# Motherboard.net
KiCad netlist of a schematic drawn in Altium Designer
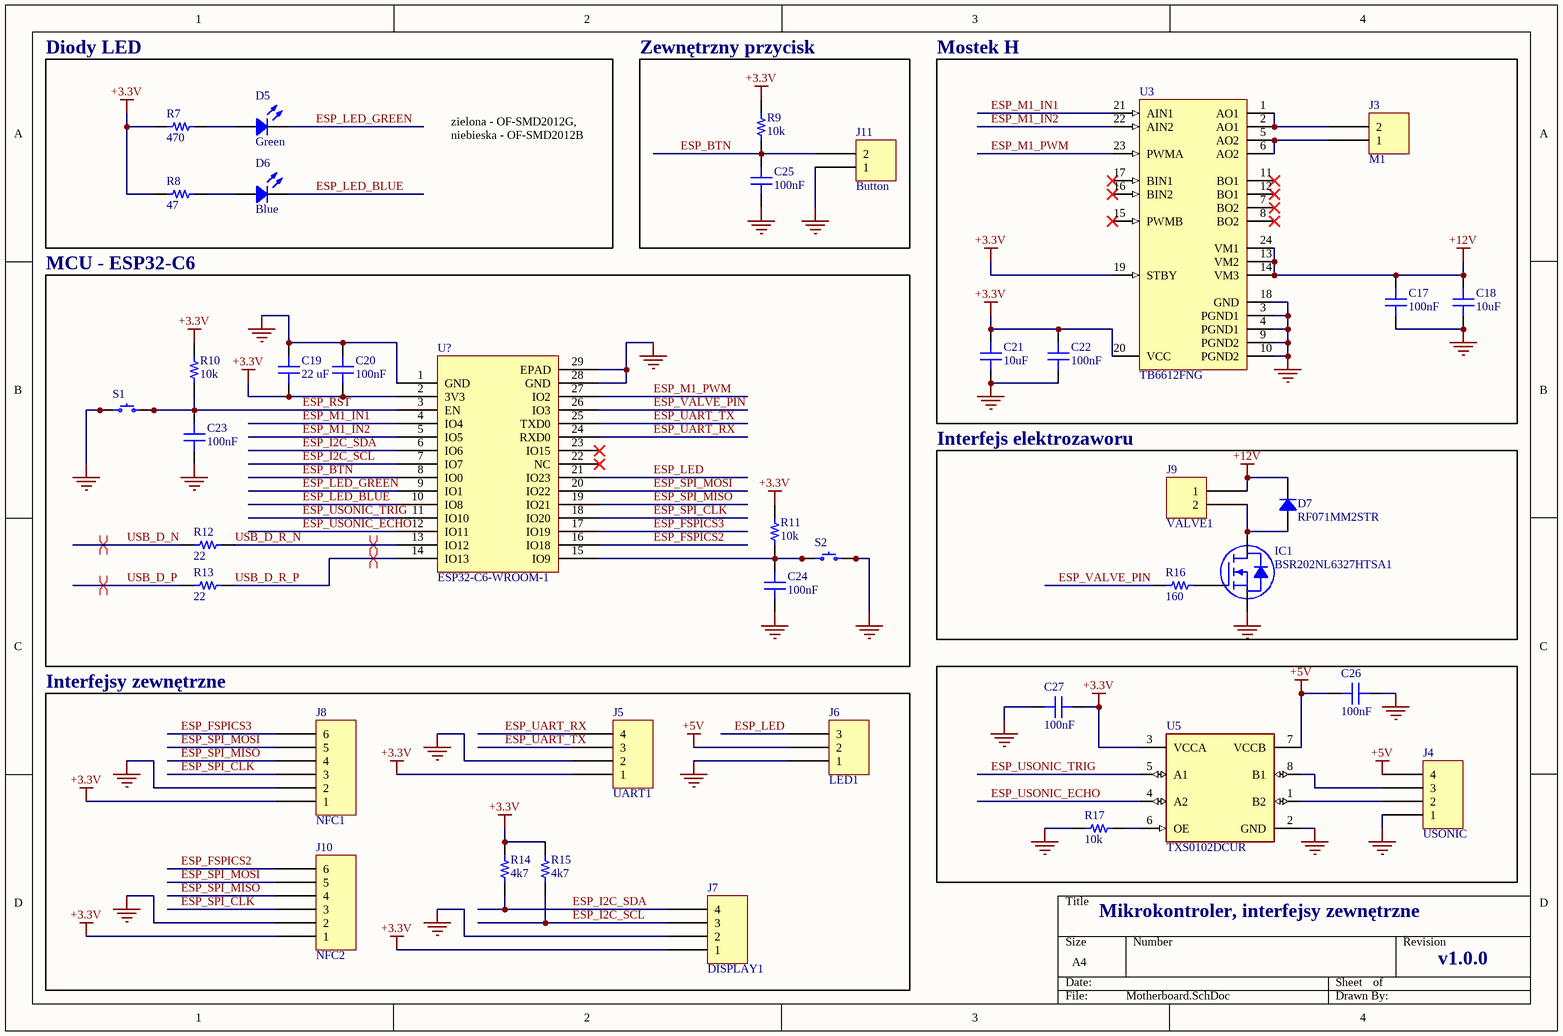
[diagram p0: Motherboard.SchDoc]

(export (version "E")
  (design (tool "Eeschema 10.0.6"))
  (components
    (comp (ref "C17")
      (value "0.1 µF")
      (footprint "CAP 0805_2012")
      (description "CAP CER 0.1UF 50V X7R 0805")
      (fields
        (field (name "PART NUMBER") "CC0805MRX7R9BB104")
        (field (name "CAPACITANCE") "100nF")
        (field (name "MANUFACTURER") "Yageo")
      )
      (libsource (lib "Celestial Altium Library - altium_library") (part "Capacitor"))
    )
    (comp (ref "C18")
      (value "10 µF")
      (footprint "CAP 0805_2012")
      (description "CAP CER 10UF 16V X6S 0805")
      (fields
        (field (name "PART NUMBER") "C2012X6S1C106K125AC")
        (field (name "CAPACITANCE") "10uF")
        (field (name "MANUFACTURER") "TDK Corporation")
      )
      (libsource (lib "Celestial Altium Library - altium_library") (part "Capacitor"))
    )
    (comp (ref "C19")
      (value "22 µF")
      (footprint "CAP 0805_2012")
      (description "CAP CER 22UF 16V X5R 0805")
      (fields
        (field (name "PART NUMBER") "CL21A226KOQNNNG")
        (field (name "CAPACITANCE") "22 uF")
        (field (name "MANUFACTURER") "Samsung Electro-Mechanics")
      )
      (libsource (lib "Celestial Altium Library - altium_library") (part "Capacitor"))
    )
    (comp (ref "C20")
      (value "0.1 µF")
      (footprint "CAP 0805_2012")
      (description "CAP CER 0.1UF 50V X7R 0805")
      (fields
        (field (name "PART NUMBER") "CC0805MRX7R9BB104")
        (field (name "CAPACITANCE") "100nF")
        (field (name "MANUFACTURER") "Yageo")
      )
      (libsource (lib "Celestial Altium Library - altium_library") (part "Capacitor"))
    )
    (comp (ref "C21")
      (value "10 µF")
      (footprint "CAP 0805_2012")
      (description "CAP CER 10UF 16V X6S 0805")
      (fields
        (field (name "PART NUMBER") "C2012X6S1C106K125AC")
        (field (name "CAPACITANCE") "10uF")
        (field (name "MANUFACTURER") "TDK Corporation")
      )
      (libsource (lib "Celestial Altium Library - altium_library") (part "Capacitor"))
    )
    (comp (ref "C22")
      (value "0.1 µF")
      (footprint "CAP 0805_2012")
      (description "CAP CER 0.1UF 50V X7R 0805")
      (fields
        (field (name "PART NUMBER") "CC0805MRX7R9BB104")
        (field (name "CAPACITANCE") "100nF")
        (field (name "MANUFACTURER") "Yageo")
      )
      (libsource (lib "Celestial Altium Library - altium_library") (part "Capacitor"))
    )
    (comp (ref "C23")
      (value "0.1 µF")
      (footprint "CAP 0805_2012")
      (description "CAP CER 0.1UF 50V X7R 0805")
      (fields
        (field (name "PART NUMBER") "CC0805MRX7R9BB104")
        (field (name "CAPACITANCE") "100nF")
        (field (name "MANUFACTURER") "Yageo")
      )
      (libsource (lib "Celestial Altium Library - altium_library") (part "Capacitor"))
    )
    (comp (ref "C24")
      (value "0.1 µF")
      (footprint "CAP 0805_2012")
      (description "CAP CER 0.1UF 50V X7R 0805")
      (fields
        (field (name "PART NUMBER") "CC0805MRX7R9BB104")
        (field (name "CAPACITANCE") "100nF")
        (field (name "MANUFACTURER") "Yageo")
      )
      (libsource (lib "Celestial Altium Library - altium_library") (part "Capacitor"))
    )
    (comp (ref "C25")
      (value "0.1 µF")
      (footprint "CAP 0805_2012")
      (description "CAP CER 0.1UF 50V X7R 0805")
      (fields
        (field (name "PART NUMBER") "CC0805MRX7R9BB104")
        (field (name "CAPACITANCE") "100nF")
        (field (name "MANUFACTURER") "Yageo")
      )
      (libsource (lib "Celestial Altium Library - altium_library") (part "Capacitor"))
    )
    (comp (ref "C26")
      (value "0.1 µF")
      (footprint "CAP 0805_2012")
      (description "CAP CER 0.1UF 50V X7R 0805")
      (fields
        (field (name "PART NUMBER") "CC0805MRX7R9BB104")
        (field (name "CAPACITANCE") "100nF")
        (field (name "MANUFACTURER") "Yageo")
      )
      (libsource (lib "Celestial Altium Library - altium_library") (part "Capacitor"))
    )
    (comp (ref "C27")
      (value "0.1 µF")
      (footprint "CAP 0805_2012")
      (description "CAP CER 0.1UF 50V X7R 0805")
      (fields
        (field (name "PART NUMBER") "CC0805MRX7R9BB104")
        (field (name "CAPACITANCE") "100nF")
        (field (name "MANUFACTURER") "Yageo")
      )
      (libsource (lib "Celestial Altium Library - altium_library") (part "Capacitor"))
    )
    (comp (ref "D5")
      (value "Green")
      (footprint "LED 0805_2012 GREEN")
      (description "LED GREEN CLEAR CHIP SMD")
      (fields (field (name "PART NUMBER") "APHCM2012CGCK-F01") (field (name "MANUFACTURER") "Kingbright"))
      (libsource (lib "Celestial Altium Library - altium_library") (part "LED"))
    )
    (comp (ref "D6")
      (value "Blue")
      (footprint "LED 0805_2012 BLUE")
      (description "LED BLUE CLEAR 2012 SMD")
      (fields (field (name "PART NUMBER") "SMLMN2BCTT86C") (field (name "MANUFACTURER") "Rohm Semiconductor"))
      (libsource (lib "Celestial Altium Library - altium_library") (part "LED"))
    )
    (comp (ref "D7")
      (value "RF071MM2STR")
      (footprint "SOD123F")
      (description "DIODE GEN PURP 200V 700MA PMDU")
      (fields (field (name "MANUFACTURER") "Rohm Semiconductor"))
      (libsource (lib "Celestial Altium Library - altium_library") (part "Diode"))
    )
    (comp (ref "IC1")
      (value "BSR202NL6327HTSA1")
      (footprint "INFINEON SOT-23-3")
      (description "MOSFET N-CH 20V 3.8A SC59")
      (fields (field (name "MANUFACTURER") "Infineon Technologies"))
      (libsource (lib "Celestial Altium Library - altium_library") (part "INFINEON MOSFET N-CH SOT-23-3 GSD"))
    )
    (comp (ref "J3")
      (value "M1")
      (footprint "MOLEX KK 0022272021")
      (description "CONN HEADER VERT 2POS 2.54MM")
      (fields (field (name "PART NUMBER") "0022272021") (field (name "MANUFACTURER") "Molex"))
      (libsource (lib "Celestial Altium Library - altium_library") (part "2 Pin"))
    )
    (comp (ref "J4")
      (value "USONIC")
      (footprint "MOLEX KK 0022272041")
      (description "CONN HEADER VERT 4POS 2.54MM")
      (fields (field (name "PART NUMBER") "0022272041") (field (name "MANUFACTURER") "Molex"))
      (libsource (lib "Celestial Altium Library - altium_library") (part "4 Pin"))
    )
    (comp (ref "J5")
      (value "UART1")
      (footprint "MOLEX KK 0022272041")
      (description "CONN HEADER VERT 4POS 2.54MM")
      (fields (field (name "PART NUMBER") "0022272041") (field (name "MANUFACTURER") "Molex"))
      (libsource (lib "Celestial Altium Library - altium_library") (part "4 Pin"))
    )
    (comp (ref "J6")
      (value "LED1")
      (footprint "MOLEX KK 0022272031")
      (description "CONN HEADER VERT 3POS 2.54MM")
      (fields (field (name "PART NUMBER") "0022272031") (field (name "MANUFACTURER") "Molex"))
      (libsource (lib "Celestial Altium Library - altium_library") (part "3 Pin"))
    )
    (comp (ref "J7")
      (value "DISPLAY1")
      (footprint "MOLEX KK 0022272041")
      (description "CONN HEADER VERT 4POS 2.54MM")
      (fields (field (name "PART NUMBER") "0022272041") (field (name "MANUFACTURER") "Molex"))
      (libsource (lib "Celestial Altium Library - altium_library") (part "4 Pin"))
    )
    (comp (ref "J8")
      (value "NFC1")
      (footprint "MOLEX KK 0022272061")
      (description "CONN HEADER VERT 6POS 2.54MM")
      (fields (field (name "PART NUMBER") "0022272061") (field (name "MANUFACTURER") "Molex"))
      (libsource (lib "Celestial Altium Library - altium_library") (part "6 Pin"))
    )
    (comp (ref "J9")
      (value "VALVE1")
      (footprint "MOLEX KK 0022272021")
      (description "CONN HEADER VERT 2POS 2.54MM")
      (fields (field (name "PART NUMBER") "0022272021") (field (name "MANUFACTURER") "Molex"))
      (libsource (lib "") (part "2 Pin_1"))
    )
    (comp (ref "J10")
      (value "NFC2")
      (footprint "MOLEX KK 0022272061")
      (description "CONN HEADER VERT 6POS 2.54MM")
      (fields (field (name "PART NUMBER") "0022272061") (field (name "MANUFACTURER") "Molex"))
      (libsource (lib "Celestial Altium Library - altium_library") (part "6 Pin"))
    )
    (comp (ref "J11")
      (value "Button")
      (footprint "MOLEX KK 0022272021")
      (description "CONN HEADER VERT 2POS 2.54MM")
      (fields (field (name "PART NUMBER") "0022272021") (field (name "MANUFACTURER") "Molex"))
      (libsource (lib "Celestial Altium Library - altium_library") (part "2 Pin"))
    )
    (comp (ref "R7")
      (value "470")
      (footprint "RES 0805_2012")
      (description "RES 470 OHM 1% 1/3W 0805")
      (fields
        (field (name "PART NUMBER") "CRGP0805F470R")
        (field (name "MANUFACTURER") "TE Connectivity Passive Product")
      )
      (libsource (lib "Celestial Altium Library - altium_library") (part "Resistor"))
    )
    (comp (ref "R8")
      (value "47")
      (footprint "RES 0805_2012")
      (description "RES 47 OHM 1% 1/3W 0805")
      (fields
        (field (name "PART NUMBER") "CRGP0805F47R")
        (field (name "MANUFACTURER") "TE Connectivity Passive Product")
      )
      (libsource (lib "Celestial Altium Library - altium_library") (part "Resistor"))
    )
    (comp (ref "R9")
      (value "10k")
      (footprint "RES 0805_2012")
      (description "RES 10K OHM 0.1% 1/10W 0805")
      (fields
        (field (name "PART NUMBER") "RNCS0805BKE10K0")
        (field (name "MANUFACTURER") "Stackpole Electronics Inc")
      )
      (libsource (lib "Celestial Altium Library - altium_library") (part "Resistor"))
    )
    (comp (ref "R10")
      (value "10k")
      (footprint "RES 0805_2012")
      (description "RES 10K OHM 0.1% 1/10W 0805")
      (fields
        (field (name "PART NUMBER") "RNCS0805BKE10K0")
        (field (name "MANUFACTURER") "Stackpole Electronics Inc")
      )
      (libsource (lib "Celestial Altium Library - altium_library") (part "Resistor"))
    )
    (comp (ref "R11")
      (value "10k")
      (footprint "RES 0805_2012")
      (description "RES 10K OHM 0.1% 1/10W 0805")
      (fields
        (field (name "PART NUMBER") "RNCS0805BKE10K0")
        (field (name "MANUFACTURER") "Stackpole Electronics Inc")
      )
      (libsource (lib "Celestial Altium Library - altium_library") (part "Resistor"))
    )
    (comp (ref "R12")
      (value "22")
      (footprint "RES 0805_2012")
      (description "RES SMD 22 OHM 0.1% 1/10W 0805")
      (fields
        (field (name "PART NUMBER") "CPF0805B22RE1")
        (field (name "MANUFACTURER") "TE Connectivity Passive Product")
      )
      (libsource (lib "Celestial Altium Library - altium_library") (part "Resistor"))
    )
    (comp (ref "R13")
      (value "22")
      (footprint "RES 0805_2012")
      (description "RES SMD 22 OHM 0.1% 1/10W 0805")
      (fields
        (field (name "PART NUMBER") "CPF0805B22RE1")
        (field (name "MANUFACTURER") "TE Connectivity Passive Product")
      )
      (libsource (lib "Celestial Altium Library - altium_library") (part "Resistor"))
    )
    (comp (ref "R14")
      (value "4k7")
      (footprint "RES 0805_2012")
      (description "RES SMD 4.7K OHM 5% 1/2W 0805")
      (fields (field (name "PART NUMBER") "RCS08054K70JNEA") (field (name "MANUFACTURER") "Vishay Dale"))
      (libsource (lib "Celestial Altium Library - altium_library") (part "Resistor"))
    )
    (comp (ref "R15")
      (value "4k7")
      (footprint "RES 0805_2012")
      (description "RES SMD 4.7K OHM 5% 1/2W 0805")
      (fields (field (name "PART NUMBER") "RCS08054K70JNEA") (field (name "MANUFACTURER") "Vishay Dale"))
      (libsource (lib "Celestial Altium Library - altium_library") (part "Resistor"))
    )
    (comp (ref "R16")
      (value "160")
      (footprint "YAGEO RES 0805_2012")
      (description "RES SMD 160 OHM 0.1% 1/8W 0805")
      (fields (field (name "PART NUMBER") "RT0805BRD07160RL") (field (name "MANUFACTURER") "Yageo"))
      (libsource (lib "Celestial Altium Library - altium_library") (part "Resistor"))
    )
    (comp (ref "R17")
      (value "10k")
      (footprint "RES 0805_2012")
      (description "RES 10K OHM 0.1% 1/10W 0805")
      (fields
        (field (name "PART NUMBER") "RNCS0805BKE10K0")
        (field (name "MANUFACTURER") "Stackpole Electronics Inc")
      )
      (libsource (lib "Celestial Altium Library - altium_library") (part "Resistor"))
    )
    (comp (ref "S1")
      (value "FSM6JSMAASTR")
      (footprint "TE FSM6JSMA")
      (description "SWITCH TACTILE SPST-NO 0.05A 24V")
      (fields (field (name "MANUFACTURER") "TE Connectivity ALCOSWITCH Switches"))
      (libsource (lib "Celestial Altium Library - altium_library") (part "SPST-NO 4 PIN"))
    )
    (comp (ref "S2")
      (value "FSM6JSMAASTR")
      (footprint "TE FSM6JSMA")
      (description "SWITCH TACTILE SPST-NO 0.05A 24V")
      (fields (field (name "MANUFACTURER") "TE Connectivity ALCOSWITCH Switches"))
      (libsource (lib "Celestial Altium Library - altium_library") (part "SPST-NO 4 PIN"))
    )
    (comp (ref "U3")
      (value "TB6612FNG")
      (footprint "TOSH-SSOP-24_M")
      (description "Driver IC for Dual DC Motor, 15 V, -20 to 85 degC, 24-Pin SSOP, RoHS, Tape and Reel")
      (libsource (lib "Altium Content Vault") (part "TOSH-TB6612FNG-SOP-24"))
    )
    (comp (ref "U4")
      (value "ESP32-C6-WROOM-1")
      (footprint "ESP32-C6-WROOM1")
      (libsource (lib "My_integrated_circuits") (part "ESP32-C6-WROOM-1"))
    )
    (comp (ref "U5")
      (value "TXS0102DCUR")
      (footprint "FP-DCU0008A-MFG")
      (description "TXS0102 2-Bit Bidirectional Voltage-Level Translator for Open-Drain and Push-Pull Applications")
      (fields (field (name "MANUFACTURER") "Texas Instruments"))
      (libsource (lib "Altium Content Vault") (part "7edb3aeb21a89e92b7ef258fabac7d1"))
    )
  )
  (nets
    (net (code "1") (name "+3.3V") (class "Default")
      (node (ref "C19") (pin "1") (pinfunction "1_1") (pintype "passive"))
      (node (ref "C20") (pin "1") (pinfunction "1_1") (pintype "passive"))
      (node (ref "C21") (pin "2") (pinfunction "2_2") (pintype "passive"))
      (node (ref "C22") (pin "1") (pinfunction "1_1") (pintype "passive"))
      (node (ref "C27") (pin "2") (pinfunction "2_2") (pintype "passive"))
      (node (ref "J10") (pin "1") (pinfunction "1_1") (pintype "passive"))
      (node (ref "J5") (pin "1") (pinfunction "1_1") (pintype "passive"))
      (node (ref "J7") (pin "1") (pinfunction "1_1") (pintype "passive"))
      (node (ref "J8") (pin "1") (pinfunction "1_1") (pintype "passive"))
      (node (ref "R10") (pin "2") (pinfunction "2_2") (pintype "passive"))
      (node (ref "R11") (pin "2") (pinfunction "2_2") (pintype "passive"))
      (node (ref "R14") (pin "2") (pinfunction "2_2") (pintype "passive"))
      (node (ref "R15") (pin "2") (pinfunction "2_2") (pintype "passive"))
      (node (ref "R7") (pin "1") (pinfunction "1_1") (pintype "passive"))
      (node (ref "R8") (pin "1") (pinfunction "1_1") (pintype "passive"))
      (node (ref "R9") (pin "2") (pinfunction "2_2") (pintype "passive"))
      (node (ref "U3") (pin "19") (pinfunction "STBY_19") (pintype "input"))
      (node (ref "U3") (pin "20") (pinfunction "VCC_20") (pintype "power_in"))
      (node (ref "U4") (pin "2") (pinfunction "3V3_2") (pintype "passive"))
      (node (ref "U5") (pin "3") (pinfunction "VCCA_3") (pintype "power_in"))
    )
    (net (code "2") (name "+5V") (class "Default")
      (node (ref "C26") (pin "1") (pinfunction "1_1") (pintype "passive"))
      (node (ref "J4") (pin "4") (pinfunction "4_4") (pintype "passive"))
      (node (ref "J6") (pin "2") (pinfunction "2_2") (pintype "passive"))
      (node (ref "U5") (pin "7") (pinfunction "VCCB_7") (pintype "power_in"))
    )
    (net (code "3") (name "+12V") (class "Default")
      (node (ref "C17") (pin "1") (pinfunction "1_1") (pintype "passive"))
      (node (ref "C18") (pin "2") (pinfunction "2_2") (pintype "passive"))
      (node (ref "D7") (pin "2") (pinfunction "2_2") (pintype "passive"))
      (node (ref "J9") (pin "1") (pinfunction "1_1") (pintype "passive"))
      (node (ref "U3") (pin "13") (pinfunction "VM2_13") (pintype "power_in"))
      (node (ref "U3") (pin "14") (pinfunction "VM3_14") (pintype "power_in"))
      (node (ref "U3") (pin "24") (pinfunction "VM1_24") (pintype "power_in"))
    )
    (net (code "4") (name "/ESP_BTN") (class "Default")
      (node (ref "C25") (pin "2") (pinfunction "2_2") (pintype "passive"))
      (node (ref "J11") (pin "2") (pinfunction "2_2") (pintype "passive"))
      (node (ref "R9") (pin "1") (pinfunction "1_1") (pintype "passive"))
      (node (ref "U4") (pin "8") (pinfunction "IO0_8") (pintype "passive"))
    )
    (net (code "5") (name "/ESP_FSPICS2") (class "Default")
      (node (ref "J10") (pin "6") (pinfunction "6_6") (pintype "passive"))
      (node (ref "U4") (pin "16") (pinfunction "IO18_16") (pintype "passive"))
    )
    (net (code "6") (name "/ESP_FSPICS3") (class "Default")
      (node (ref "J8") (pin "6") (pinfunction "6_6") (pintype "passive"))
      (node (ref "U4") (pin "17") (pinfunction "IO19_17") (pintype "passive"))
    )
    (net (code "7") (name "/ESP_I2C_SCL") (class "Default")
      (node (ref "J7") (pin "3") (pinfunction "3_3") (pintype "passive"))
      (node (ref "R15") (pin "1") (pinfunction "1_1") (pintype "passive"))
      (node (ref "U4") (pin "7") (pinfunction "IO7_7") (pintype "passive"))
    )
    (net (code "8") (name "/ESP_I2C_SDA") (class "Default")
      (node (ref "J7") (pin "4") (pinfunction "4_4") (pintype "passive"))
      (node (ref "R14") (pin "1") (pinfunction "1_1") (pintype "passive"))
      (node (ref "U4") (pin "6") (pinfunction "IO6_6") (pintype "passive"))
    )
    (net (code "9") (name "/ESP_LED") (class "Default")
      (node (ref "J6") (pin "3") (pinfunction "3_3") (pintype "passive"))
      (node (ref "U4") (pin "21") (pinfunction "IO23_21") (pintype "passive"))
    )
    (net (code "10") (name "/ESP_LED_BLUE") (class "Default")
      (node (ref "D6") (pin "2") (pinfunction "2_2") (pintype "passive"))
      (node (ref "U4") (pin "10") (pinfunction "IO8_10") (pintype "passive"))
    )
    (net (code "11") (name "/ESP_LED_GREEN") (class "Default")
      (node (ref "D5") (pin "2") (pinfunction "2_2") (pintype "passive"))
      (node (ref "U4") (pin "9") (pinfunction "IO1_9") (pintype "passive"))
    )
    (net (code "12") (name "/ESP_M1_IN1") (class "Default")
      (node (ref "U3") (pin "21") (pinfunction "AIN1_21") (pintype "input"))
      (node (ref "U4") (pin "4") (pinfunction "IO4_4") (pintype "passive"))
    )
    (net (code "13") (name "/ESP_M1_IN2") (class "Default")
      (node (ref "U3") (pin "22") (pinfunction "AIN2_22") (pintype "input"))
      (node (ref "U4") (pin "5") (pinfunction "IO5_5") (pintype "passive"))
    )
    (net (code "14") (name "/ESP_M1_PWM") (class "Default")
      (node (ref "U3") (pin "23") (pinfunction "PWMA_23") (pintype "input"))
      (node (ref "U4") (pin "27") (pinfunction "IO2_27") (pintype "passive"))
    )
    (net (code "15") (name "/ESP_RST") (class "Default")
      (node (ref "C23") (pin "2") (pinfunction "2_2") (pintype "passive"))
      (node (ref "R10") (pin "1") (pinfunction "1_1") (pintype "passive"))
      (node (ref "S1") (pin "3") (pinfunction "3_3") (pintype "passive"))
      (node (ref "S1") (pin "4") (pinfunction "4_4") (pintype "passive"))
      (node (ref "U4") (pin "3") (pinfunction "EN_3") (pintype "passive"))
    )
    (net (code "16") (name "/ESP_SPI_CLK") (class "Default")
      (node (ref "J10") (pin "3") (pinfunction "3_3") (pintype "passive"))
      (node (ref "J8") (pin "3") (pinfunction "3_3") (pintype "passive"))
      (node (ref "U4") (pin "18") (pinfunction "IO20_18") (pintype "passive"))
    )
    (net (code "17") (name "/ESP_SPI_MISO") (class "Default")
      (node (ref "J10") (pin "4") (pinfunction "4_4") (pintype "passive"))
      (node (ref "J8") (pin "4") (pinfunction "4_4") (pintype "passive"))
      (node (ref "U4") (pin "19") (pinfunction "IO21_19") (pintype "passive"))
    )
    (net (code "18") (name "/ESP_SPI_MOSI") (class "Default")
      (node (ref "J10") (pin "5") (pinfunction "5_5") (pintype "passive"))
      (node (ref "J8") (pin "5") (pinfunction "5_5") (pintype "passive"))
      (node (ref "U4") (pin "20") (pinfunction "IO22_20") (pintype "passive"))
    )
    (net (code "19") (name "/ESP_UART_RX") (class "Default")
      (node (ref "J5") (pin "4") (pinfunction "4_4") (pintype "passive"))
      (node (ref "U4") (pin "24") (pinfunction "RXD0_24") (pintype "passive"))
    )
    (net (code "20") (name "/ESP_UART_TX") (class "Default")
      (node (ref "J5") (pin "3") (pinfunction "3_3") (pintype "passive"))
      (node (ref "U4") (pin "25") (pinfunction "TXD0_25") (pintype "passive"))
    )
    (net (code "21") (name "/ESP_USONIC_ECHO") (class "Default")
      (node (ref "U4") (pin "12") (pinfunction "IO11_12") (pintype "passive"))
      (node (ref "U5") (pin "4") (pinfunction "A2_4") (pintype "bidirectional"))
    )
    (net (code "22") (name "/ESP_USONIC_TRIG") (class "Default")
      (node (ref "U4") (pin "11") (pinfunction "IO10_11") (pintype "passive"))
      (node (ref "U5") (pin "5") (pinfunction "A1_5") (pintype "bidirectional"))
    )
    (net (code "23") (name "/ESP_VALVE_PIN") (class "Default")
      (node (ref "R16") (pin "1") (pinfunction "1_1") (pintype "passive"))
      (node (ref "U4") (pin "26") (pinfunction "IO3_26") (pintype "passive"))
    )
    (net (code "24") (name "/USB_D_N") (class "Default")
      (node (ref "R12") (pin "1") (pinfunction "1_1") (pintype "passive"))
    )
    (net (code "25") (name "/USB_D_P") (class "Default")
      (node (ref "R13") (pin "1") (pinfunction "1_1") (pintype "passive"))
    )
    (net (code "26") (name "/USB_D_R_N") (class "Default")
      (node (ref "R12") (pin "2") (pinfunction "2_2") (pintype "passive"))
      (node (ref "U4") (pin "13") (pinfunction "IO12_13") (pintype "passive"))
    )
    (net (code "27") (name "/USB_D_R_P") (class "Default")
      (node (ref "R13") (pin "2") (pinfunction "2_2") (pintype "passive"))
      (node (ref "U4") (pin "14") (pinfunction "IO13_14") (pintype "passive"))
    )
    (net (code "28") (name "GND") (class "Default")
      (node (ref "C17") (pin "2") (pinfunction "2_2") (pintype "passive"))
      (node (ref "C18") (pin "1") (pinfunction "1_1") (pintype "passive"))
      (node (ref "C19") (pin "2") (pinfunction "2_2") (pintype "passive"))
      (node (ref "C20") (pin "2") (pinfunction "2_2") (pintype "passive"))
      (node (ref "C21") (pin "1") (pinfunction "1_1") (pintype "passive"))
      (node (ref "C22") (pin "2") (pinfunction "2_2") (pintype "passive"))
      (node (ref "C23") (pin "1") (pinfunction "1_1") (pintype "passive"))
      (node (ref "C24") (pin "1") (pinfunction "1_1") (pintype "passive"))
      (node (ref "C25") (pin "1") (pinfunction "1_1") (pintype "passive"))
      (node (ref "C26") (pin "2") (pinfunction "2_2") (pintype "passive"))
      (node (ref "C27") (pin "1") (pinfunction "1_1") (pintype "passive"))
      (node (ref "IC1") (pin "2") (pinfunction "S_2") (pintype "passive"))
      (node (ref "J10") (pin "2") (pinfunction "2_2") (pintype "passive"))
      (node (ref "J11") (pin "1") (pinfunction "1_1") (pintype "passive"))
      (node (ref "J4") (pin "1") (pinfunction "1_1") (pintype "passive"))
      (node (ref "J5") (pin "2") (pinfunction "2_2") (pintype "passive"))
      (node (ref "J6") (pin "1") (pinfunction "1_1") (pintype "passive"))
      (node (ref "J7") (pin "2") (pinfunction "2_2") (pintype "passive"))
      (node (ref "J8") (pin "2") (pinfunction "2_2") (pintype "passive"))
      (node (ref "R17") (pin "1") (pinfunction "1_1") (pintype "passive"))
      (node (ref "S1") (pin "1") (pinfunction "1_1") (pintype "passive"))
      (node (ref "S1") (pin "2") (pinfunction "2_2") (pintype "passive"))
      (node (ref "S2") (pin "3") (pinfunction "3_3") (pintype "passive"))
      (node (ref "S2") (pin "4") (pinfunction "4_4") (pintype "passive"))
      (node (ref "U3") (pin "10") (pinfunction "PGND2_10") (pintype "power_in"))
      (node (ref "U3") (pin "18") (pinfunction "GND_18") (pintype "power_in"))
      (node (ref "U3") (pin "3") (pinfunction "PGND1_3") (pintype "power_in"))
      (node (ref "U3") (pin "4") (pinfunction "PGND1_4") (pintype "power_in"))
      (node (ref "U3") (pin "9") (pinfunction "PGND2_9") (pintype "power_in"))
      (node (ref "U4") (pin "1") (pinfunction "GND_1") (pintype "passive"))
      (node (ref "U4") (pin "28") (pinfunction "GND_28") (pintype "passive"))
      (node (ref "U4") (pin "29") (pinfunction "EPAD_29") (pintype "passive"))
      (node (ref "U5") (pin "2") (pinfunction "GND_2") (pintype "power_in"))
    )
    (net (code "29") (name "Net-(D5-Pad1)") (class "Default")
      (node (ref "D5") (pin "1") (pinfunction "1_1") (pintype "passive"))
      (node (ref "R7") (pin "2") (pinfunction "2_2") (pintype "passive"))
    )
    (net (code "30") (name "Net-(D6-Pad1)") (class "Default")
      (node (ref "D6") (pin "1") (pinfunction "1_1") (pintype "passive"))
      (node (ref "R8") (pin "2") (pinfunction "2_2") (pintype "passive"))
    )
    (net (code "31") (name "Net-(IC1-D)") (class "Default")
      (node (ref "D7") (pin "1") (pinfunction "1_1") (pintype "passive"))
      (node (ref "IC1") (pin "3") (pinfunction "D_3") (pintype "passive"))
      (node (ref "J9") (pin "2") (pinfunction "2_2") (pintype "passive"))
    )
    (net (code "32") (name "Net-(IC1-G)") (class "Default")
      (node (ref "IC1") (pin "1") (pinfunction "G_1") (pintype "passive"))
      (node (ref "R16") (pin "2") (pinfunction "2_2") (pintype "passive"))
    )
    (net (code "33") (name "Net-(J3-Pad1)") (class "Default")
      (node (ref "J3") (pin "1") (pinfunction "1_1") (pintype "passive"))
      (node (ref "U3") (pin "5") (pinfunction "AO2_5") (pintype "tri_state"))
      (node (ref "U3") (pin "6") (pinfunction "AO2_6") (pintype "tri_state"))
    )
    (net (code "34") (name "Net-(J3-Pad2)") (class "Default")
      (node (ref "J3") (pin "2") (pinfunction "2_2") (pintype "passive"))
      (node (ref "U3") (pin "1") (pinfunction "AO1_1") (pintype "tri_state"))
      (node (ref "U3") (pin "2") (pinfunction "AO1_2") (pintype "tri_state"))
    )
    (net (code "35") (name "Net-(U4-IO9)") (class "Default")
      (node (ref "C24") (pin "2") (pinfunction "2_2") (pintype "passive"))
      (node (ref "R11") (pin "1") (pinfunction "1_1") (pintype "passive"))
      (node (ref "S2") (pin "1") (pinfunction "1_1") (pintype "passive"))
      (node (ref "S2") (pin "2") (pinfunction "2_2") (pintype "passive"))
      (node (ref "U4") (pin "15") (pinfunction "IO9_15") (pintype "passive"))
    )
    (net (code "36") (name "Net-(U5-B1)") (class "Default")
      (node (ref "J4") (pin "3") (pinfunction "3_3") (pintype "passive"))
      (node (ref "U5") (pin "8") (pinfunction "B1_8") (pintype "bidirectional"))
    )
    (net (code "37") (name "Net-(U5-B2)") (class "Default")
      (node (ref "J4") (pin "2") (pinfunction "2_2") (pintype "passive"))
      (node (ref "U5") (pin "1") (pinfunction "B2_1") (pintype "bidirectional"))
    )
    (net (code "38") (name "Net-(U5-OE)") (class "Default")
      (node (ref "R17") (pin "2") (pinfunction "2_2") (pintype "passive"))
      (node (ref "U5") (pin "6") (pinfunction "OE_6") (pintype "input"))
    )
    (net (code "39") (name "unconnected-(U3-BIN1-Pad17)") (class "Default")
      (node (ref "U3") (pin "17") (pinfunction "BIN1_17") (pintype "input+no_connect"))
    )
    (net (code "40") (name "unconnected-(U3-BIN2-Pad16)") (class "Default")
      (node (ref "U3") (pin "16") (pinfunction "BIN2_16") (pintype "input+no_connect"))
    )
    (net (code "41") (name "unconnected-(U3-BO1-Pad11)") (class "Default")
      (node (ref "U3") (pin "11") (pinfunction "BO1_11") (pintype "tri_state+no_connect"))
    )
    (net (code "42") (name "unconnected-(U3-BO1-Pad12)") (class "Default")
      (node (ref "U3") (pin "12") (pinfunction "BO1_12") (pintype "tri_state+no_connect"))
    )
    (net (code "43") (name "unconnected-(U3-BO2-Pad7)") (class "Default")
      (node (ref "U3") (pin "7") (pinfunction "BO2_7") (pintype "tri_state+no_connect"))
    )
    (net (code "44") (name "unconnected-(U3-BO2-Pad8)") (class "Default")
      (node (ref "U3") (pin "8") (pinfunction "BO2_8") (pintype "tri_state+no_connect"))
    )
    (net (code "45") (name "unconnected-(U3-PWMB-Pad15)") (class "Default")
      (node (ref "U3") (pin "15") (pinfunction "PWMB_15") (pintype "input+no_connect"))
    )
    (net (code "46") (name "unconnected-(U4-IO15-Pad23)") (class "Default")
      (node (ref "U4") (pin "23") (pinfunction "IO15_23") (pintype "passive+no_connect"))
    )
    (net (code "47") (name "unconnected-(U4-NC-Pad22)") (class "Default")
      (node (ref "U4") (pin "22") (pinfunction "NC_22") (pintype "passive+no_connect"))
    )
  )
)
